# Pwr.net
KiCad netlist of a schematic drawn in Altium Designer
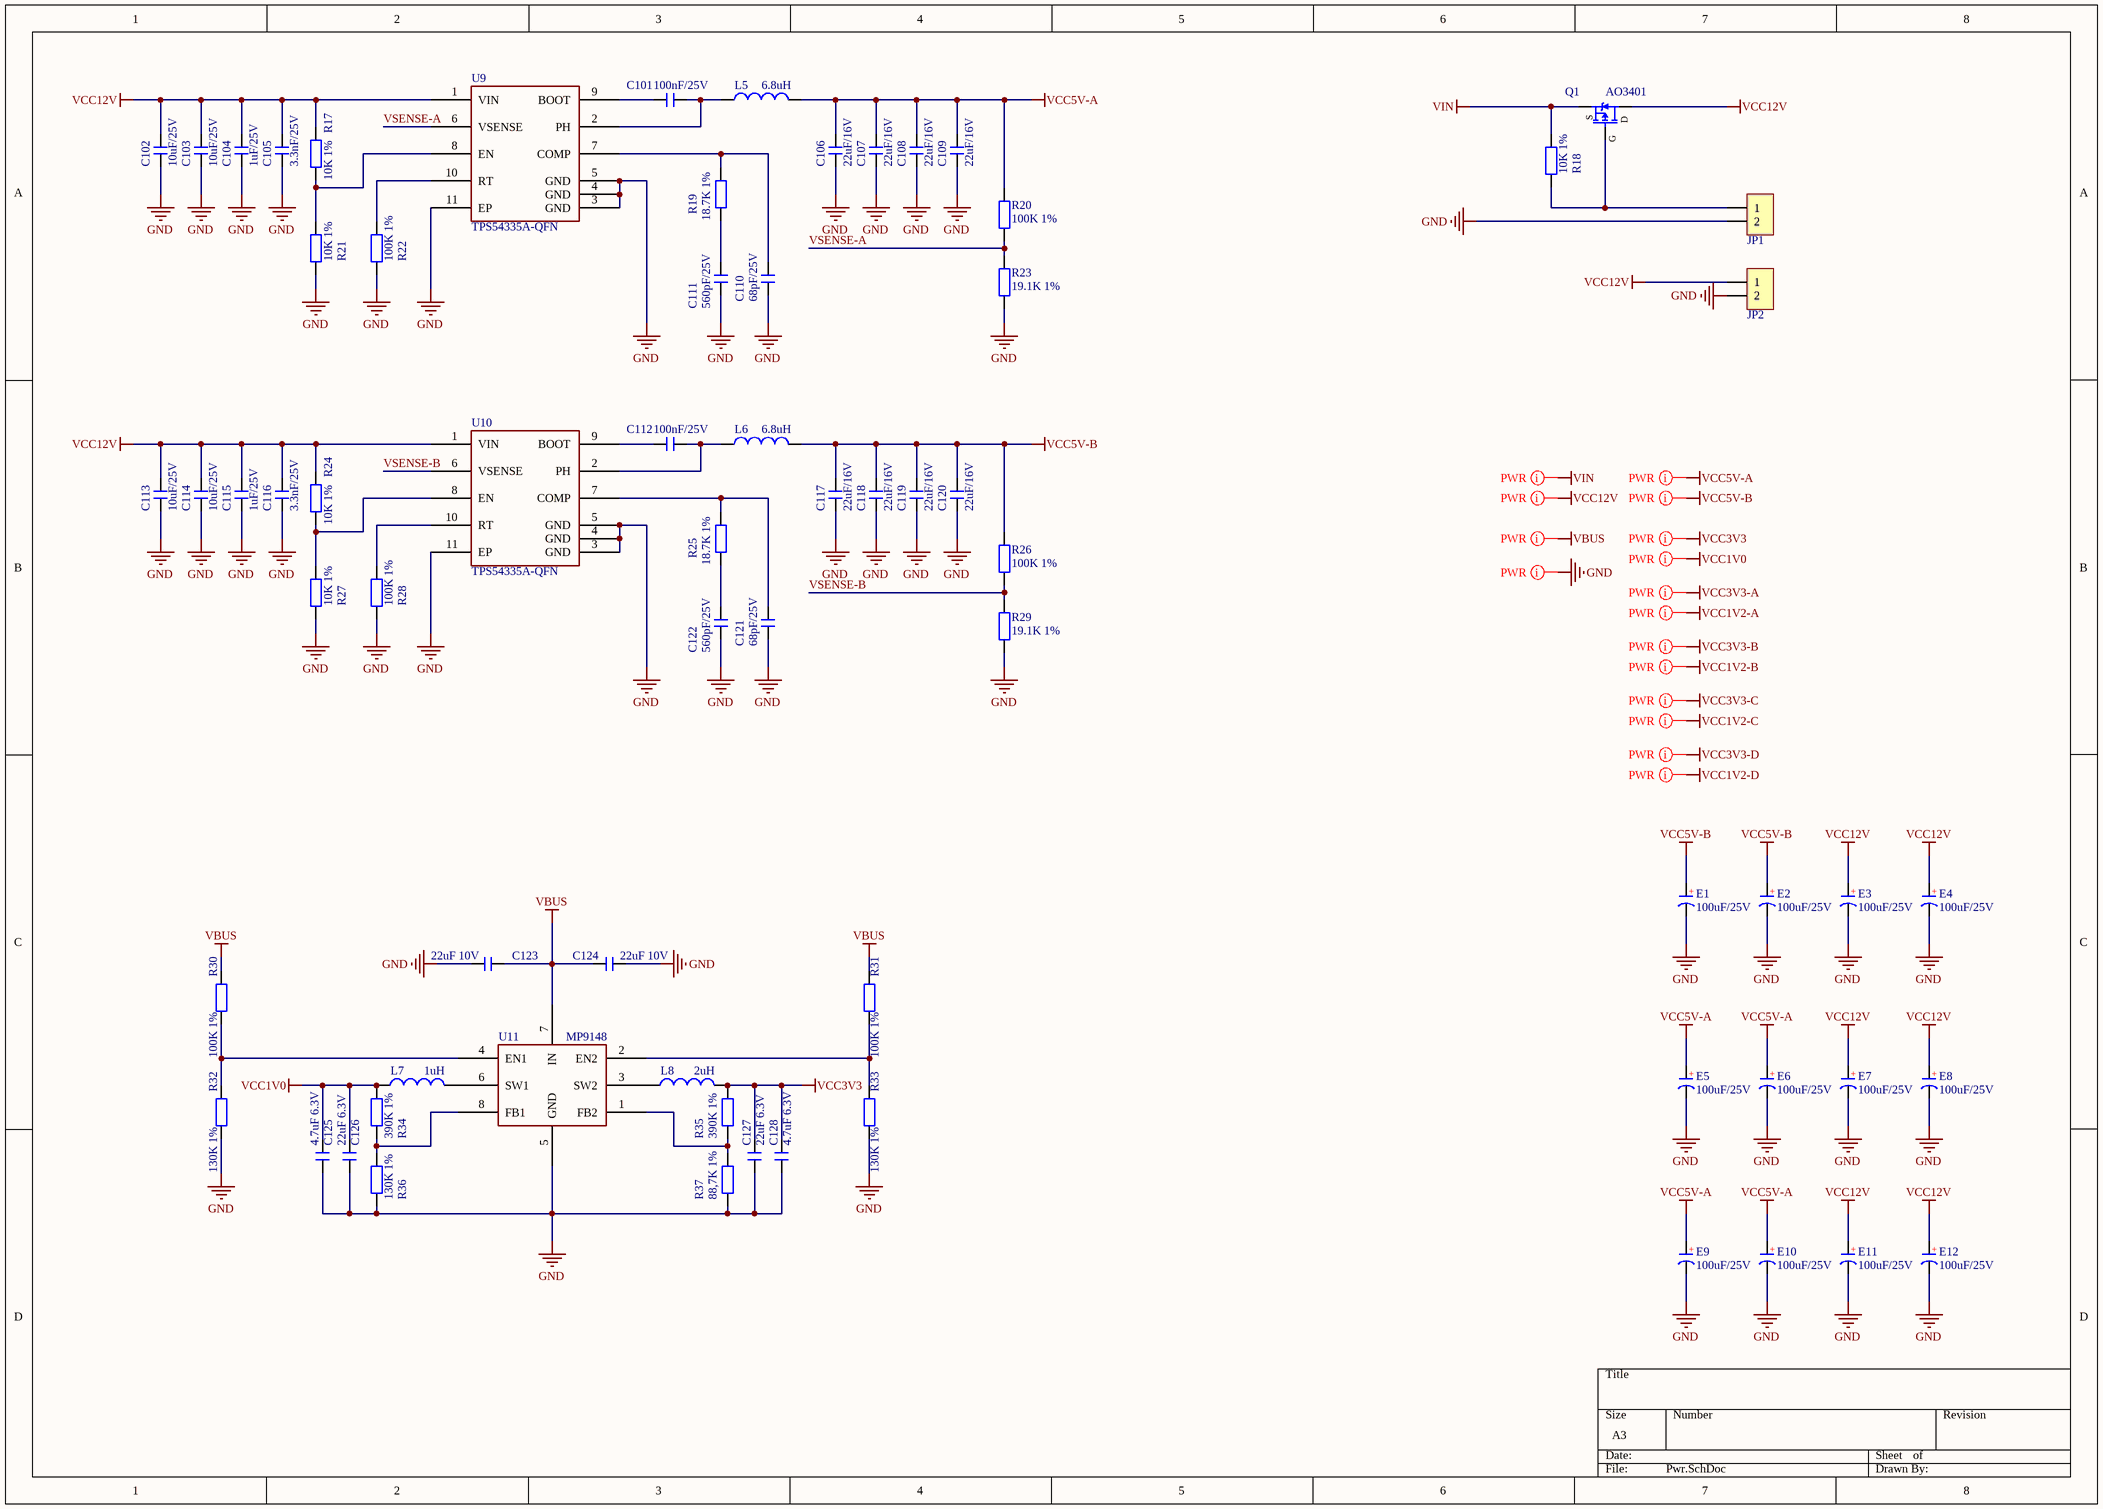
[diagram p0: Pwr.SchDoc]

(export (version "E")
  (design (tool "Eeschema 10.0.6"))
  (components
    (comp (ref "C101")
      (value "100nF/25V")
      (footprint "C0402_L")
      (description "无极性贴片电容")
      (fields (field (name "版权归属") "源创客"))
      (libsource (lib "Capacitor") (part "C"))
    )
    (comp (ref "C102")
      (value "10uF/25V")
      (footprint "C0603_L")
      (description "无极性贴片电容")
      (fields (field (name "版权归属") "源创客"))
      (libsource (lib "Capacitor") (part "C"))
    )
    (comp (ref "C103")
      (value "10uF/25V")
      (footprint "C0603_L")
      (description "无极性贴片电容")
      (fields (field (name "版权归属") "源创客"))
      (libsource (lib "Capacitor") (part "C"))
    )
    (comp (ref "C104")
      (value "1uF/25V")
      (footprint "C0603_L")
      (description "无极性贴片电容")
      (fields (field (name "版权归属") "源创客"))
      (libsource (lib "Capacitor") (part "C"))
    )
    (comp (ref "C105")
      (value "3.3nF/25V")
      (footprint "C0603_L")
      (description "无极性贴片电容")
      (fields (field (name "版权归属") "源创客"))
      (libsource (lib "Capacitor") (part "C"))
    )
    (comp (ref "C106")
      (value "22uF/16V")
      (footprint "C0603_L")
      (description "无极性贴片电容")
      (fields (field (name "版权归属") "源创客"))
      (libsource (lib "Capacitor") (part "C"))
    )
    (comp (ref "C107")
      (value "22uF/16V")
      (footprint "C0603_L")
      (description "无极性贴片电容")
      (fields (field (name "版权归属") "源创客"))
      (libsource (lib "Capacitor") (part "C"))
    )
    (comp (ref "C108")
      (value "22uF/16V")
      (footprint "C0603_L")
      (description "无极性贴片电容")
      (fields (field (name "版权归属") "源创客"))
      (libsource (lib "Capacitor") (part "C"))
    )
    (comp (ref "C109")
      (value "22uF/16V")
      (footprint "C0603_L")
      (description "无极性贴片电容")
      (fields (field (name "版权归属") "源创客"))
      (libsource (lib "Capacitor") (part "C"))
    )
    (comp (ref "C110")
      (value "68pF/25V")
      (footprint "C0402_L")
      (description "无极性贴片电容")
      (fields (field (name "版权归属") "源创客"))
      (libsource (lib "Capacitor") (part "C"))
    )
    (comp (ref "C111")
      (value "560pF/25V")
      (footprint "C0402_L")
      (description "无极性贴片电容")
      (fields (field (name "版权归属") "源创客"))
      (libsource (lib "Capacitor") (part "C"))
    )
    (comp (ref "C112")
      (value "100nF/25V")
      (footprint "C0402_L")
      (description "无极性贴片电容")
      (fields (field (name "版权归属") "源创客"))
      (libsource (lib "Capacitor") (part "C"))
    )
    (comp (ref "C113")
      (value "10uF/25V")
      (footprint "C0603_L")
      (description "无极性贴片电容")
      (fields (field (name "版权归属") "源创客"))
      (libsource (lib "Capacitor") (part "C"))
    )
    (comp (ref "C114")
      (value "10uF/25V")
      (footprint "C0603_L")
      (description "无极性贴片电容")
      (fields (field (name "版权归属") "源创客"))
      (libsource (lib "Capacitor") (part "C"))
    )
    (comp (ref "C115")
      (value "1uF/25V")
      (footprint "C0603_L")
      (description "无极性贴片电容")
      (fields (field (name "版权归属") "源创客"))
      (libsource (lib "Capacitor") (part "C"))
    )
    (comp (ref "C116")
      (value "3.3nF/25V")
      (footprint "C0603_L")
      (description "无极性贴片电容")
      (fields (field (name "版权归属") "源创客"))
      (libsource (lib "Capacitor") (part "C"))
    )
    (comp (ref "C117")
      (value "22uF/16V")
      (footprint "C0603_L")
      (description "无极性贴片电容")
      (fields (field (name "版权归属") "源创客"))
      (libsource (lib "Capacitor") (part "C"))
    )
    (comp (ref "C118")
      (value "22uF/16V")
      (footprint "C0603_L")
      (description "无极性贴片电容")
      (fields (field (name "版权归属") "源创客"))
      (libsource (lib "Capacitor") (part "C"))
    )
    (comp (ref "C119")
      (value "22uF/16V")
      (footprint "C0603_L")
      (description "无极性贴片电容")
      (fields (field (name "版权归属") "源创客"))
      (libsource (lib "Capacitor") (part "C"))
    )
    (comp (ref "C120")
      (value "22uF/16V")
      (footprint "C0603_L")
      (description "无极性贴片电容")
      (fields (field (name "版权归属") "源创客"))
      (libsource (lib "Capacitor") (part "C"))
    )
    (comp (ref "C121")
      (value "68pF/25V")
      (footprint "C0402_L")
      (description "无极性贴片电容")
      (fields (field (name "版权归属") "源创客"))
      (libsource (lib "Capacitor") (part "C"))
    )
    (comp (ref "C122")
      (value "560pF/25V")
      (footprint "C0402_L")
      (description "无极性贴片电容")
      (fields (field (name "版权归属") "源创客"))
      (libsource (lib "Capacitor") (part "C"))
    )
    (comp (ref "C123")
      (value "22uF 10V")
      (footprint "C0603_L")
      (description "无极性贴片电容")
      (fields (field (name "版权归属") "源创客"))
      (libsource (lib "Capacitor") (part "C"))
    )
    (comp (ref "C124")
      (value "22uF 10V")
      (footprint "C0603_L")
      (description "无极性贴片电容")
      (fields (field (name "版权归属") "源创客"))
      (libsource (lib "Capacitor") (part "C"))
    )
    (comp (ref "C125")
      (value "4.7uF 6.3V")
      (footprint "C0603_L")
      (description "无极性贴片电容")
      (fields (field (name "版权归属") "源创客"))
      (libsource (lib "Capacitor") (part "C"))
    )
    (comp (ref "C126")
      (value "22uF 6.3V")
      (footprint "C0603_L")
      (description "无极性贴片电容")
      (fields (field (name "版权归属") "源创客"))
      (libsource (lib "Capacitor") (part "C"))
    )
    (comp (ref "C127")
      (value "22uF 6.3V")
      (footprint "C0603_L")
      (description "无极性贴片电容")
      (fields (field (name "版权归属") "源创客"))
      (libsource (lib "Capacitor") (part "C"))
    )
    (comp (ref "C128")
      (value "4.7uF 6.3V")
      (footprint "C0603_L")
      (description "无极性贴片电容")
      (fields (field (name "版权归属") "源创客"))
      (libsource (lib "Capacitor") (part "C"))
    )
    (comp (ref "E1")
      (value "100uF/25V")
      (footprint "CS 6*4 - B")
      (description "贴片钽电容")
      (fields (field (name "版权归属") "源创客"))
      (libsource (lib "Capacitor") (part "C-CD"))
    )
    (comp (ref "E2")
      (value "100uF/25V")
      (footprint "CS 6*4 - B")
      (description "贴片钽电容")
      (fields (field (name "版权归属") "源创客"))
      (libsource (lib "Capacitor") (part "C-CD"))
    )
    (comp (ref "E3")
      (value "100uF/25V")
      (footprint "CS 6*4 - B")
      (description "贴片钽电容")
      (fields (field (name "版权归属") "源创客"))
      (libsource (lib "Capacitor") (part "C-CD"))
    )
    (comp (ref "E4")
      (value "100uF/25V")
      (footprint "CS 6*4 - B")
      (description "贴片钽电容")
      (fields (field (name "版权归属") "源创客"))
      (libsource (lib "Capacitor") (part "C-CD"))
    )
    (comp (ref "E5")
      (value "100uF/25V")
      (footprint "CS 6*4 - B")
      (description "贴片钽电容")
      (fields (field (name "版权归属") "源创客"))
      (libsource (lib "Capacitor") (part "C-CD"))
    )
    (comp (ref "E6")
      (value "100uF/25V")
      (footprint "CS 6*4 - B")
      (description "贴片钽电容")
      (fields (field (name "版权归属") "源创客"))
      (libsource (lib "Capacitor") (part "C-CD"))
    )
    (comp (ref "E7")
      (value "100uF/25V")
      (footprint "CS 6*4 - B")
      (description "贴片钽电容")
      (fields (field (name "版权归属") "源创客"))
      (libsource (lib "Capacitor") (part "C-CD"))
    )
    (comp (ref "E8")
      (value "100uF/25V")
      (footprint "CS 6*4 - B")
      (description "贴片钽电容")
      (fields (field (name "版权归属") "源创客"))
      (libsource (lib "Capacitor") (part "C-CD"))
    )
    (comp (ref "E9")
      (value "100uF/25V")
      (footprint "CS 6*4 - B")
      (description "贴片钽电容")
      (fields (field (name "版权归属") "源创客"))
      (libsource (lib "Capacitor") (part "C-CD"))
    )
    (comp (ref "E10")
      (value "100uF/25V")
      (footprint "CS 6*4 - B")
      (description "贴片钽电容")
      (fields (field (name "版权归属") "源创客"))
      (libsource (lib "Capacitor") (part "C-CD"))
    )
    (comp (ref "E11")
      (value "100uF/25V")
      (footprint "CS 6*4 - B")
      (description "贴片钽电容")
      (fields (field (name "版权归属") "源创客"))
      (libsource (lib "Capacitor") (part "C-CD"))
    )
    (comp (ref "E12")
      (value "100uF/25V")
      (footprint "CS 6*4 - B")
      (description "贴片钽电容")
      (fields (field (name "版权归属") "源创客"))
      (libsource (lib "Capacitor") (part "C-CD"))
    )
    (comp (ref "JP1")
      (value "HDR-1X2")
      (footprint "ZH1.5-WS-2P")
      (description "2P接插件")
      (fields (field (name "版权归属") "源创客"))
      (libsource (lib "Connector-PinHeader") (part "Header 2"))
    )
    (comp (ref "JP2")
      (value "HDR-1X2")
      (footprint "XH2.54-WS-2P")
      (description "2P接插件")
      (fields (field (name "版权归属") "源创客"))
      (libsource (lib "Connector-PinHeader") (part "Header 2"))
    )
    (comp (ref "L5")
      (value "6.8uH")
      (footprint "NR4020")
      (description "小功率贴片电感")
      (fields (field (name "版权归属") "源创客"))
      (libsource (lib "Inductor") (part "L"))
    )
    (comp (ref "L6")
      (value "6.8uH")
      (footprint "NR4020")
      (description "小功率贴片电感")
      (fields (field (name "版权归属") "源创客"))
      (libsource (lib "Inductor") (part "L"))
    )
    (comp (ref "L7")
      (value "1uH")
      (footprint "NR4020")
      (description "小功率贴片电感")
      (fields (field (name "版权归属") "源创客"))
      (libsource (lib "Inductor") (part "L"))
    )
    (comp (ref "L8")
      (value "2uH")
      (footprint "NR4020")
      (description "小功率贴片电感")
      (fields (field (name "版权归属") "源创客"))
      (libsource (lib "") (part "L_1"))
    )
    (comp (ref "Q1")
      (value "AO3401")
      (footprint "DFN8-L3.0-W3.0-P0.65_EP")
      (description "P沟道 30V/4.2A")
      (fields (field (name "版权归属") "源创客"))
      (libsource (lib "MOSFET BJT IGBT") (part "AO3401"))
    )
    (comp (ref "R17")
      (value "10K 1%")
      (footprint "R0402_L")
      (description "贴片电阻")
      (fields (field (name "版权归属") "源创客"))
      (libsource (lib "Resistor") (part "R"))
    )
    (comp (ref "R18")
      (value "10K 1%")
      (footprint "R0402_L")
      (description "贴片电阻")
      (fields (field (name "版权归属") "源创客"))
      (libsource (lib "Resistor") (part "R"))
    )
    (comp (ref "R19")
      (value "18.7K 1%")
      (footprint "R0402_L")
      (description "贴片电阻")
      (fields (field (name "版权归属") "源创客"))
      (libsource (lib "Resistor") (part "R"))
    )
    (comp (ref "R20")
      (value "100K 1%")
      (footprint "R0402_L")
      (description "贴片电阻")
      (fields (field (name "版权归属") "源创客"))
      (libsource (lib "Resistor") (part "R"))
    )
    (comp (ref "R21")
      (value "10K 1%")
      (footprint "R0402_L")
      (description "贴片电阻")
      (fields (field (name "版权归属") "源创客"))
      (libsource (lib "Resistor") (part "R"))
    )
    (comp (ref "R22")
      (value "100K 1%")
      (footprint "R0402_L")
      (description "贴片电阻")
      (fields (field (name "版权归属") "源创客"))
      (libsource (lib "Resistor") (part "R"))
    )
    (comp (ref "R23")
      (value "19.1K 1%")
      (footprint "R0402_L")
      (description "贴片电阻")
      (fields (field (name "版权归属") "源创客"))
      (libsource (lib "Resistor") (part "R"))
    )
    (comp (ref "R24")
      (value "10K 1%")
      (footprint "R0402_L")
      (description "贴片电阻")
      (fields (field (name "版权归属") "源创客"))
      (libsource (lib "Resistor") (part "R"))
    )
    (comp (ref "R25")
      (value "18.7K 1%")
      (footprint "R0402_L")
      (description "贴片电阻")
      (fields (field (name "版权归属") "源创客"))
      (libsource (lib "Resistor") (part "R"))
    )
    (comp (ref "R26")
      (value "100K 1%")
      (footprint "R0402_L")
      (description "贴片电阻")
      (fields (field (name "版权归属") "源创客"))
      (libsource (lib "Resistor") (part "R"))
    )
    (comp (ref "R27")
      (value "10K 1%")
      (footprint "R0402_L")
      (description "贴片电阻")
      (fields (field (name "版权归属") "源创客"))
      (libsource (lib "Resistor") (part "R"))
    )
    (comp (ref "R28")
      (value "100K 1%")
      (footprint "R0402_L")
      (description "贴片电阻")
      (fields (field (name "版权归属") "源创客"))
      (libsource (lib "Resistor") (part "R"))
    )
    (comp (ref "R29")
      (value "19.1K 1%")
      (footprint "R0402_L")
      (description "贴片电阻")
      (fields (field (name "版权归属") "源创客"))
      (libsource (lib "Resistor") (part "R"))
    )
    (comp (ref "R30")
      (value "100K 1%")
      (footprint "R0402_L")
      (description "贴片电阻")
      (fields (field (name "版权归属") "源创客"))
      (libsource (lib "Resistor") (part "R"))
    )
    (comp (ref "R31")
      (value "100K 1%")
      (footprint "R0402_L")
      (description "贴片电阻")
      (fields (field (name "版权归属") "源创客"))
      (libsource (lib "Resistor") (part "R"))
    )
    (comp (ref "R32")
      (value "130K 1%")
      (footprint "R0402_L")
      (description "贴片电阻")
      (fields (field (name "版权归属") "源创客"))
      (libsource (lib "Resistor") (part "R"))
    )
    (comp (ref "R33")
      (value "130K 1%")
      (footprint "R0402_L")
      (description "贴片电阻")
      (fields (field (name "版权归属") "源创客"))
      (libsource (lib "Resistor") (part "R"))
    )
    (comp (ref "R34")
      (value "390K 1%")
      (footprint "R0402_L")
      (description "贴片电阻")
      (fields (field (name "版权归属") "源创客"))
      (libsource (lib "Resistor") (part "R"))
    )
    (comp (ref "R35")
      (value "390K 1%")
      (footprint "R0402_L")
      (description "贴片电阻")
      (fields (field (name "版权归属") "源创客"))
      (libsource (lib "Resistor") (part "R"))
    )
    (comp (ref "R36")
      (value "130K 1%")
      (footprint "R0402_L")
      (description "贴片电阻")
      (fields (field (name "版权归属") "源创客"))
      (libsource (lib "Resistor") (part "R"))
    )
    (comp (ref "R37")
      (value "88,7K 1%")
      (footprint "R0402_L")
      (description "贴片电阻")
      (fields (field (name "版权归属") "源创客"))
      (libsource (lib "Resistor") (part "R"))
    )
    (comp (ref "U9")
      (value "TPS54335A-QFN")
      (footprint "VSON-10_L3.0-W3.0-P0.50-TL-EP")
      (description "BUCK")
      (libsource (lib "DCDC Convert") (part "TPS54335A-QFN"))
    )
    (comp (ref "U10")
      (value "TPS54335A-QFN")
      (footprint "VSON-10_L3.0-W3.0-P0.50-TL-EP")
      (description "BUCK")
      (libsource (lib "DCDC Convert") (part "TPS54335A-QFN"))
    )
    (comp (ref "U11")
      (value "MP9148")
      (footprint "SOT23-8")
      (description "BUCK")
      (libsource (lib "DCDC Convert") (part "MP9148"))
    )
  )
  (nets
    (net (code "1") (name "/VSENSE-A") (class "Default")
      (node (ref "R20") (pin "2") (pinfunction "2_2") (pintype "passive"))
      (node (ref "R23") (pin "1") (pinfunction "1_1") (pintype "passive"))
      (node (ref "U9") (pin "6") (pinfunction "VSENSE_6") (pintype "passive"))
    )
    (net (code "2") (name "/VSENSE-B") (class "Default")
      (node (ref "R26") (pin "2") (pinfunction "2_2") (pintype "passive"))
      (node (ref "R29") (pin "1") (pinfunction "1_1") (pintype "passive"))
      (node (ref "U10") (pin "6") (pinfunction "VSENSE_6") (pintype "passive"))
    )
    (net (code "3") (name "GND") (class "Default")
      (node (ref "C102") (pin "1") (pinfunction "1_1") (pintype "passive"))
      (node (ref "C103") (pin "1") (pinfunction "1_1") (pintype "passive"))
      (node (ref "C104") (pin "1") (pinfunction "1_1") (pintype "passive"))
      (node (ref "C105") (pin "1") (pinfunction "1_1") (pintype "passive"))
      (node (ref "C106") (pin "1") (pinfunction "1_1") (pintype "passive"))
      (node (ref "C107") (pin "1") (pinfunction "1_1") (pintype "passive"))
      (node (ref "C108") (pin "1") (pinfunction "1_1") (pintype "passive"))
      (node (ref "C109") (pin "1") (pinfunction "1_1") (pintype "passive"))
      (node (ref "C110") (pin "1") (pinfunction "1_1") (pintype "passive"))
      (node (ref "C111") (pin "1") (pinfunction "1_1") (pintype "passive"))
      (node (ref "C113") (pin "1") (pinfunction "1_1") (pintype "passive"))
      (node (ref "C114") (pin "1") (pinfunction "1_1") (pintype "passive"))
      (node (ref "C115") (pin "1") (pinfunction "1_1") (pintype "passive"))
      (node (ref "C116") (pin "1") (pinfunction "1_1") (pintype "passive"))
      (node (ref "C117") (pin "1") (pinfunction "1_1") (pintype "passive"))
      (node (ref "C118") (pin "1") (pinfunction "1_1") (pintype "passive"))
      (node (ref "C119") (pin "1") (pinfunction "1_1") (pintype "passive"))
      (node (ref "C120") (pin "1") (pinfunction "1_1") (pintype "passive"))
      (node (ref "C121") (pin "1") (pinfunction "1_1") (pintype "passive"))
      (node (ref "C122") (pin "1") (pinfunction "1_1") (pintype "passive"))
      (node (ref "C123") (pin "1") (pinfunction "1_1") (pintype "passive"))
      (node (ref "C124") (pin "1") (pinfunction "1_1") (pintype "passive"))
      (node (ref "C125") (pin "1") (pinfunction "1_1") (pintype "passive"))
      (node (ref "C126") (pin "1") (pinfunction "1_1") (pintype "passive"))
      (node (ref "C127") (pin "1") (pinfunction "1_1") (pintype "passive"))
      (node (ref "C128") (pin "1") (pinfunction "1_1") (pintype "passive"))
      (node (ref "E1") (pin "2") (pinfunction "K_2") (pintype "passive"))
      (node (ref "E10") (pin "2") (pinfunction "K_2") (pintype "passive"))
      (node (ref "E11") (pin "2") (pinfunction "K_2") (pintype "passive"))
      (node (ref "E12") (pin "2") (pinfunction "K_2") (pintype "passive"))
      (node (ref "E2") (pin "2") (pinfunction "K_2") (pintype "passive"))
      (node (ref "E3") (pin "2") (pinfunction "K_2") (pintype "passive"))
      (node (ref "E4") (pin "2") (pinfunction "K_2") (pintype "passive"))
      (node (ref "E5") (pin "2") (pinfunction "K_2") (pintype "passive"))
      (node (ref "E6") (pin "2") (pinfunction "K_2") (pintype "passive"))
      (node (ref "E7") (pin "2") (pinfunction "K_2") (pintype "passive"))
      (node (ref "E8") (pin "2") (pinfunction "K_2") (pintype "passive"))
      (node (ref "E9") (pin "2") (pinfunction "K_2") (pintype "passive"))
      (node (ref "JP1") (pin "2") (pinfunction "2_2") (pintype "passive"))
      (node (ref "JP2") (pin "2") (pinfunction "2_2") (pintype "passive"))
      (node (ref "R21") (pin "2") (pinfunction "2_2") (pintype "passive"))
      (node (ref "R22") (pin "2") (pinfunction "2_2") (pintype "passive"))
      (node (ref "R23") (pin "2") (pinfunction "2_2") (pintype "passive"))
      (node (ref "R27") (pin "2") (pinfunction "2_2") (pintype "passive"))
      (node (ref "R28") (pin "2") (pinfunction "2_2") (pintype "passive"))
      (node (ref "R29") (pin "2") (pinfunction "2_2") (pintype "passive"))
      (node (ref "R32") (pin "2") (pinfunction "2_2") (pintype "passive"))
      (node (ref "R33") (pin "2") (pinfunction "2_2") (pintype "passive"))
      (node (ref "R36") (pin "2") (pinfunction "2_2") (pintype "passive"))
      (node (ref "R37") (pin "2") (pinfunction "2_2") (pintype "passive"))
      (node (ref "U10") (pin "11") (pinfunction "EP_11") (pintype "passive"))
      (node (ref "U10") (pin "3") (pinfunction "GND_3") (pintype "passive"))
      (node (ref "U10") (pin "4") (pinfunction "GND_4") (pintype "passive"))
      (node (ref "U10") (pin "5") (pinfunction "GND_5") (pintype "passive"))
      (node (ref "U11") (pin "5") (pinfunction "GND_5") (pintype "passive"))
      (node (ref "U9") (pin "11") (pinfunction "EP_11") (pintype "passive"))
      (node (ref "U9") (pin "3") (pinfunction "GND_3") (pintype "passive"))
      (node (ref "U9") (pin "4") (pinfunction "GND_4") (pintype "passive"))
      (node (ref "U9") (pin "5") (pinfunction "GND_5") (pintype "passive"))
    )
    (net (code "4") (name "Net-(C111-Pad2)") (class "Default")
      (node (ref "C111") (pin "2") (pinfunction "2_2") (pintype "passive"))
      (node (ref "R19") (pin "2") (pinfunction "2_2") (pintype "passive"))
    )
    (net (code "5") (name "Net-(C122-Pad2)") (class "Default")
      (node (ref "C122") (pin "2") (pinfunction "2_2") (pintype "passive"))
      (node (ref "R25") (pin "2") (pinfunction "2_2") (pintype "passive"))
    )
    (net (code "6") (name "Net-(Q1-G)") (class "Default")
      (node (ref "JP1") (pin "1") (pinfunction "1_1") (pintype "passive"))
      (node (ref "Q1") (pin "1") (pinfunction "G_1") (pintype "passive"))
      (node (ref "R18") (pin "2") (pinfunction "2_2") (pintype "passive"))
    )
    (net (code "7") (name "Net-(U9-BOOT)") (class "Default")
      (node (ref "C101") (pin "2") (pinfunction "2_2") (pintype "passive"))
      (node (ref "U9") (pin "9") (pinfunction "BOOT_9") (pintype "passive"))
    )
    (net (code "8") (name "Net-(U9-COMP)") (class "Default")
      (node (ref "C110") (pin "2") (pinfunction "2_2") (pintype "passive"))
      (node (ref "R19") (pin "1") (pinfunction "1_1") (pintype "passive"))
      (node (ref "U9") (pin "7") (pinfunction "COMP_7") (pintype "passive"))
    )
    (net (code "9") (name "Net-(U9-EN)") (class "Default")
      (node (ref "R17") (pin "2") (pinfunction "2_2") (pintype "passive"))
      (node (ref "R21") (pin "1") (pinfunction "1_1") (pintype "passive"))
      (node (ref "U9") (pin "8") (pinfunction "EN_8") (pintype "passive"))
    )
    (net (code "10") (name "Net-(U9-PH)") (class "Default")
      (node (ref "C101") (pin "1") (pinfunction "1_1") (pintype "passive"))
      (node (ref "L5") (pin "1") (pinfunction "1_1") (pintype "passive"))
      (node (ref "U9") (pin "2") (pinfunction "PH_2") (pintype "passive"))
    )
    (net (code "11") (name "Net-(U9-RT)") (class "Default")
      (node (ref "R22") (pin "1") (pinfunction "1_1") (pintype "passive"))
      (node (ref "U9") (pin "10") (pinfunction "RT_10") (pintype "passive"))
    )
    (net (code "12") (name "Net-(U10-BOOT)") (class "Default")
      (node (ref "C112") (pin "2") (pinfunction "2_2") (pintype "passive"))
      (node (ref "U10") (pin "9") (pinfunction "BOOT_9") (pintype "passive"))
    )
    (net (code "13") (name "Net-(U10-COMP)") (class "Default")
      (node (ref "C121") (pin "2") (pinfunction "2_2") (pintype "passive"))
      (node (ref "R25") (pin "1") (pinfunction "1_1") (pintype "passive"))
      (node (ref "U10") (pin "7") (pinfunction "COMP_7") (pintype "passive"))
    )
    (net (code "14") (name "Net-(U10-EN)") (class "Default")
      (node (ref "R24") (pin "2") (pinfunction "2_2") (pintype "passive"))
      (node (ref "R27") (pin "1") (pinfunction "1_1") (pintype "passive"))
      (node (ref "U10") (pin "8") (pinfunction "EN_8") (pintype "passive"))
    )
    (net (code "15") (name "Net-(U10-PH)") (class "Default")
      (node (ref "C112") (pin "1") (pinfunction "1_1") (pintype "passive"))
      (node (ref "L6") (pin "1") (pinfunction "1_1") (pintype "passive"))
      (node (ref "U10") (pin "2") (pinfunction "PH_2") (pintype "passive"))
    )
    (net (code "16") (name "Net-(U10-RT)") (class "Default")
      (node (ref "R28") (pin "1") (pinfunction "1_1") (pintype "passive"))
      (node (ref "U10") (pin "10") (pinfunction "RT_10") (pintype "passive"))
    )
    (net (code "17") (name "Net-(U11-EN1)") (class "Default")
      (node (ref "R30") (pin "2") (pinfunction "2_2") (pintype "passive"))
      (node (ref "R32") (pin "1") (pinfunction "1_1") (pintype "passive"))
      (node (ref "U11") (pin "4") (pinfunction "EN1_4") (pintype "passive"))
    )
    (net (code "18") (name "Net-(U11-EN2)") (class "Default")
      (node (ref "R31") (pin "2") (pinfunction "2_2") (pintype "passive"))
      (node (ref "R33") (pin "1") (pinfunction "1_1") (pintype "passive"))
      (node (ref "U11") (pin "2") (pinfunction "EN2_2") (pintype "passive"))
    )
    (net (code "19") (name "Net-(U11-FB1)") (class "Default")
      (node (ref "R34") (pin "2") (pinfunction "2_2") (pintype "passive"))
      (node (ref "R36") (pin "1") (pinfunction "1_1") (pintype "passive"))
      (node (ref "U11") (pin "8") (pinfunction "FB1_8") (pintype "passive"))
    )
    (net (code "20") (name "Net-(U11-FB2)") (class "Default")
      (node (ref "R35") (pin "2") (pinfunction "2_2") (pintype "passive"))
      (node (ref "R37") (pin "1") (pinfunction "1_1") (pintype "passive"))
      (node (ref "U11") (pin "1") (pinfunction "FB2_1") (pintype "passive"))
    )
    (net (code "21") (name "Net-(U11-SW1)") (class "Default")
      (node (ref "L7") (pin "2") (pinfunction "2_2") (pintype "passive"))
      (node (ref "U11") (pin "6") (pinfunction "SW1_6") (pintype "passive"))
    )
    (net (code "22") (name "Net-(U11-SW2)") (class "Default")
      (node (ref "L8") (pin "2") (pinfunction "2_2") (pintype "passive"))
      (node (ref "U11") (pin "3") (pinfunction "SW2_3") (pintype "passive"))
    )
    (net (code "23") (name "VBUS") (class "Default")
      (node (ref "C123") (pin "2") (pinfunction "2_2") (pintype "passive"))
      (node (ref "C124") (pin "2") (pinfunction "2_2") (pintype "passive"))
      (node (ref "R30") (pin "1") (pinfunction "1_1") (pintype "passive"))
      (node (ref "R31") (pin "1") (pinfunction "1_1") (pintype "passive"))
      (node (ref "U11") (pin "7") (pinfunction "IN_7") (pintype "passive"))
    )
    (net (code "24") (name "VCC1V0") (class "Default")
      (node (ref "C125") (pin "2") (pinfunction "2_2") (pintype "passive"))
      (node (ref "C126") (pin "2") (pinfunction "2_2") (pintype "passive"))
      (node (ref "L7") (pin "1") (pinfunction "1_1") (pintype "passive"))
      (node (ref "R34") (pin "1") (pinfunction "1_1") (pintype "passive"))
    )
    (net (code "29") (name "VCC3V3") (class "Default")
      (node (ref "C127") (pin "2") (pinfunction "2_2") (pintype "passive"))
      (node (ref "C128") (pin "2") (pinfunction "2_2") (pintype "passive"))
      (node (ref "L8") (pin "1") (pinfunction "1_1") (pintype "passive"))
      (node (ref "R35") (pin "1") (pinfunction "1_1") (pintype "passive"))
    )
    (net (code "34") (name "VCC5V-A") (class "Default")
      (node (ref "C106") (pin "2") (pinfunction "2_2") (pintype "passive"))
      (node (ref "C107") (pin "2") (pinfunction "2_2") (pintype "passive"))
      (node (ref "C108") (pin "2") (pinfunction "2_2") (pintype "passive"))
      (node (ref "C109") (pin "2") (pinfunction "2_2") (pintype "passive"))
      (node (ref "E10") (pin "1") (pinfunction "A_1") (pintype "passive"))
      (node (ref "E5") (pin "1") (pinfunction "A_1") (pintype "passive"))
      (node (ref "E6") (pin "1") (pinfunction "A_1") (pintype "passive"))
      (node (ref "E9") (pin "1") (pinfunction "A_1") (pintype "passive"))
      (node (ref "L5") (pin "2") (pinfunction "2_2") (pintype "passive"))
      (node (ref "R20") (pin "1") (pinfunction "1_1") (pintype "passive"))
    )
    (net (code "35") (name "VCC5V-B") (class "Default")
      (node (ref "C117") (pin "2") (pinfunction "2_2") (pintype "passive"))
      (node (ref "C118") (pin "2") (pinfunction "2_2") (pintype "passive"))
      (node (ref "C119") (pin "2") (pinfunction "2_2") (pintype "passive"))
      (node (ref "C120") (pin "2") (pinfunction "2_2") (pintype "passive"))
      (node (ref "E1") (pin "1") (pinfunction "A_1") (pintype "passive"))
      (node (ref "E2") (pin "1") (pinfunction "A_1") (pintype "passive"))
      (node (ref "L6") (pin "2") (pinfunction "2_2") (pintype "passive"))
      (node (ref "R26") (pin "1") (pinfunction "1_1") (pintype "passive"))
    )
    (net (code "36") (name "VCC12V") (class "Default")
      (node (ref "C102") (pin "2") (pinfunction "2_2") (pintype "passive"))
      (node (ref "C103") (pin "2") (pinfunction "2_2") (pintype "passive"))
      (node (ref "C104") (pin "2") (pinfunction "2_2") (pintype "passive"))
      (node (ref "C105") (pin "2") (pinfunction "2_2") (pintype "passive"))
      (node (ref "C113") (pin "2") (pinfunction "2_2") (pintype "passive"))
      (node (ref "C114") (pin "2") (pinfunction "2_2") (pintype "passive"))
      (node (ref "C115") (pin "2") (pinfunction "2_2") (pintype "passive"))
      (node (ref "C116") (pin "2") (pinfunction "2_2") (pintype "passive"))
      (node (ref "E11") (pin "1") (pinfunction "A_1") (pintype "passive"))
      (node (ref "E12") (pin "1") (pinfunction "A_1") (pintype "passive"))
      (node (ref "E3") (pin "1") (pinfunction "A_1") (pintype "passive"))
      (node (ref "E4") (pin "1") (pinfunction "A_1") (pintype "passive"))
      (node (ref "E7") (pin "1") (pinfunction "A_1") (pintype "passive"))
      (node (ref "E8") (pin "1") (pinfunction "A_1") (pintype "passive"))
      (node (ref "JP2") (pin "1") (pinfunction "1_1") (pintype "passive"))
      (node (ref "Q1") (pin "3") (pinfunction "D_3") (pintype "passive"))
      (node (ref "R17") (pin "1") (pinfunction "1_1") (pintype "passive"))
      (node (ref "R24") (pin "1") (pinfunction "1_1") (pintype "passive"))
      (node (ref "U10") (pin "1") (pinfunction "VIN_1") (pintype "passive"))
      (node (ref "U9") (pin "1") (pinfunction "VIN_1") (pintype "passive"))
    )
    (net (code "37") (name "VIN") (class "Default")
      (node (ref "Q1") (pin "2") (pinfunction "S_2") (pintype "passive"))
      (node (ref "R18") (pin "1") (pinfunction "1_1") (pintype "passive"))
    )
  )
)
